# 1541-3z.net
KiCad netlist of a schematic drawn in EAGLE
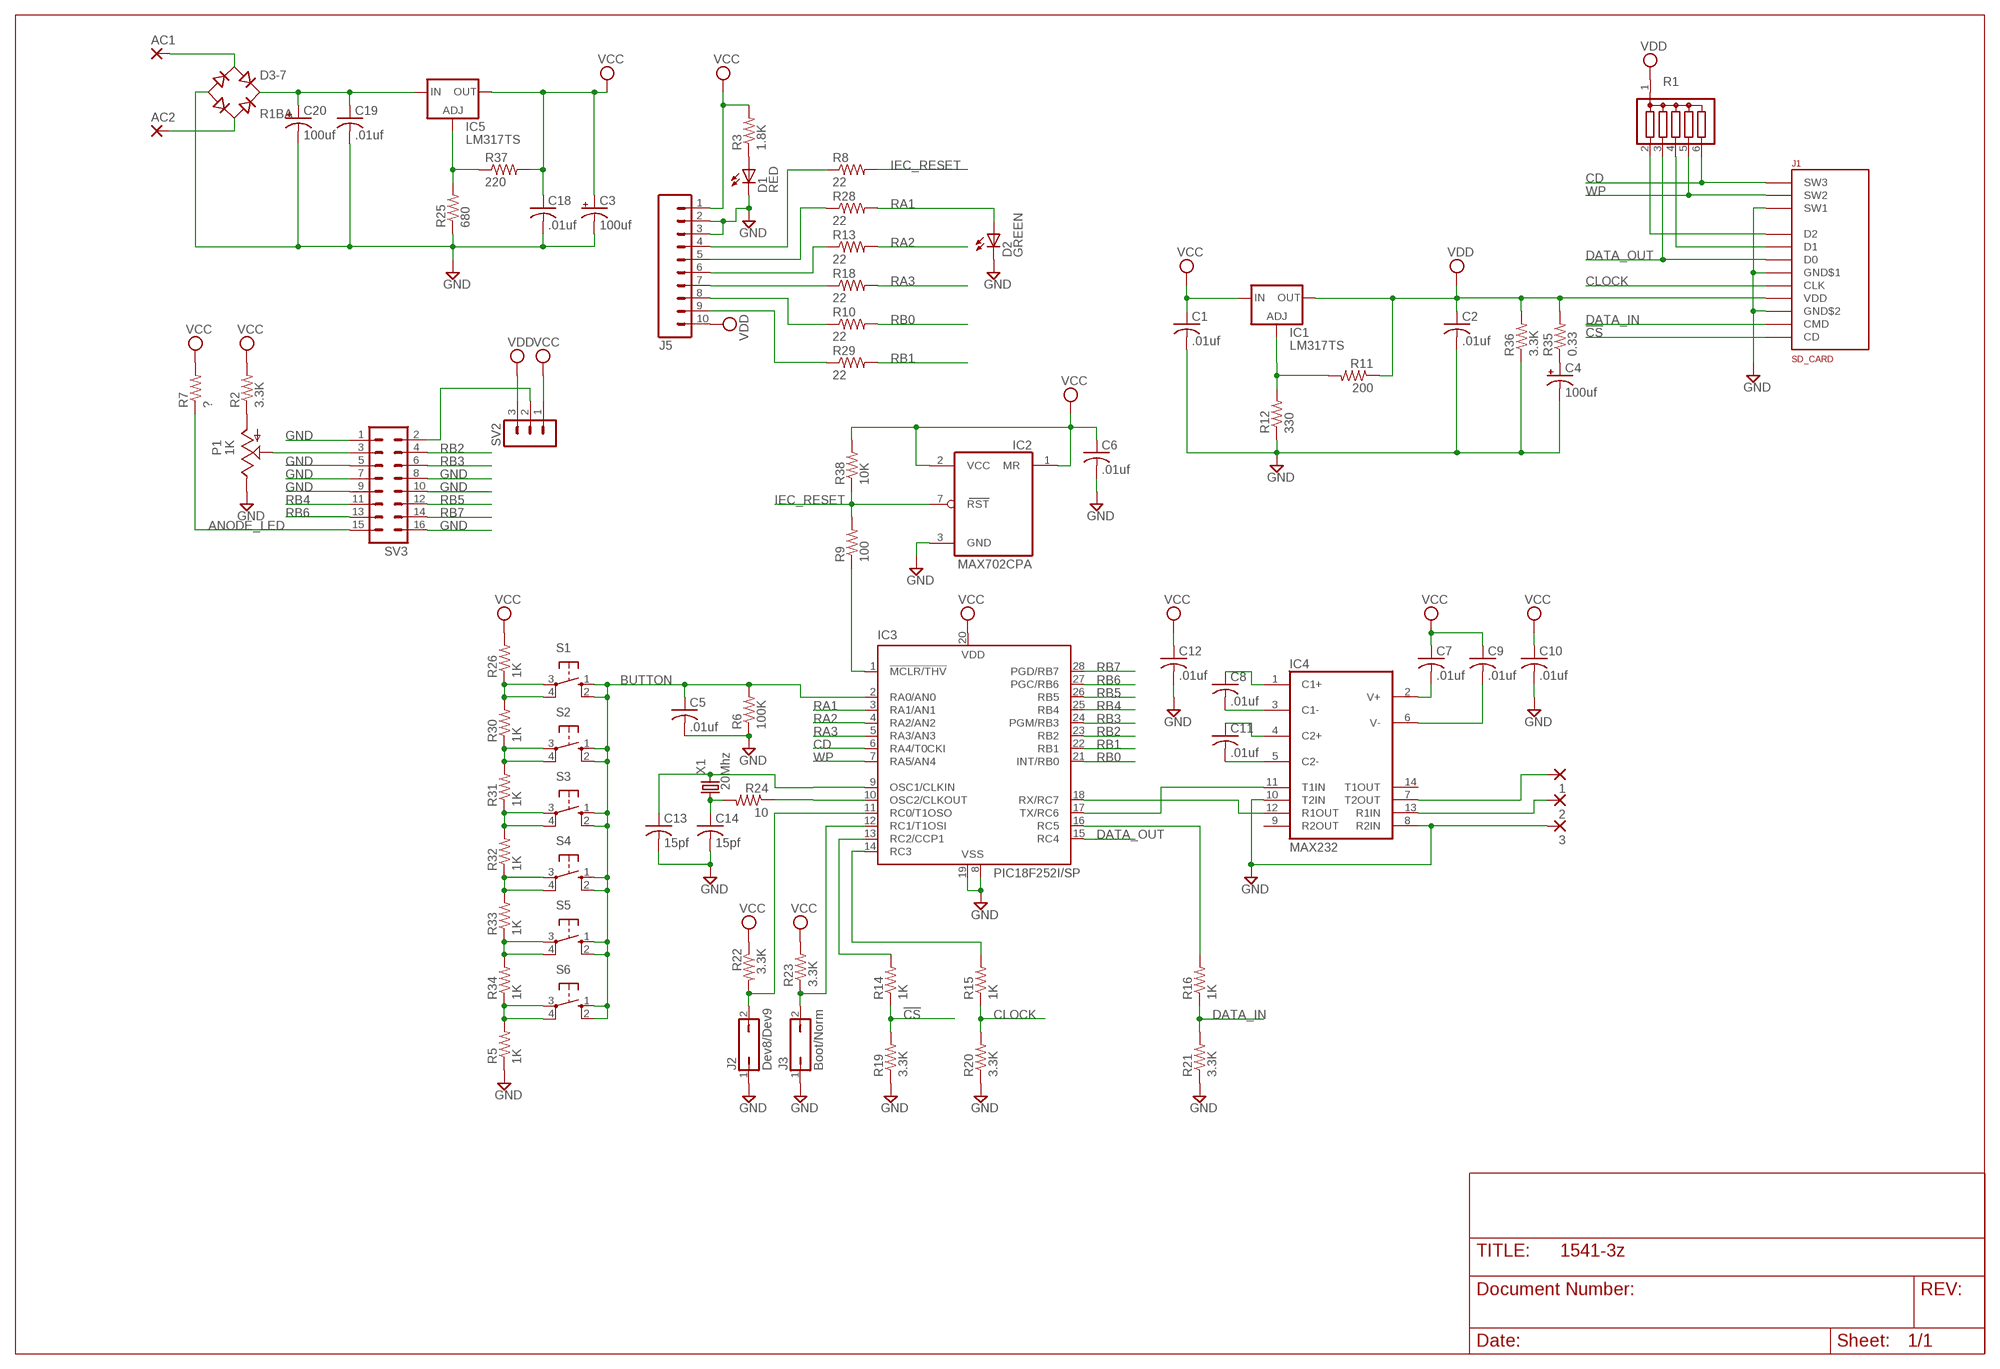
[diagram p0: schematic, sheet 1]

(export (version "E")
  (design (tool "Eeschema 10.0.6"))
  (components
    (comp (ref "1")
      (value "2,15/1,0")
      (footprint "eagle-import:2,15_1,0")
      (libsource (lib "eagle-import") (part "2,15/1,0"))
    )
    (comp (ref "2")
      (value "2,15/1,0")
      (footprint "eagle-import:2,15_1,0")
      (libsource (lib "eagle-import") (part "2,15/1,0"))
    )
    (comp (ref "3")
      (value "2,15/1,0")
      (footprint "eagle-import:2,15_1,0")
      (libsource (lib "eagle-import") (part "2,15/1,0"))
    )
    (comp (ref "AC1")
      (value "2,15/1,0")
      (footprint "eagle-import:2,15_1,0")
      (libsource (lib "eagle-import") (part "2,15/1,0"))
    )
    (comp (ref "AC2")
      (value "2,15/1,0")
      (footprint "eagle-import:2,15_1,0")
      (libsource (lib "eagle-import") (part "2,15/1,0"))
    )
    (comp (ref "C1")
      (value ".01uf")
      (footprint "eagle-import:C025-024X044")
      (libsource (lib "eagle-import") (part "C-US025-024X044"))
    )
    (comp (ref "C2")
      (value ".01uf")
      (footprint "eagle-import:C025-024X044")
      (libsource (lib "eagle-import") (part "C-US025-024X044"))
    )
    (comp (ref "C3")
      (value "100uf")
      (footprint "eagle-import:E2-5")
      (libsource (lib "eagle-import") (part "CPOL-USE2-5"))
    )
    (comp (ref "C4")
      (value "100uf")
      (footprint "eagle-import:E2-5")
      (libsource (lib "eagle-import") (part "CPOL-USE2-5"))
    )
    (comp (ref "C5")
      (value ".01uf")
      (footprint "eagle-import:C025-024X044")
      (libsource (lib "eagle-import") (part "C-US025-024X044"))
    )
    (comp (ref "C6")
      (value ".01uf")
      (footprint "eagle-import:C025-024X044")
      (libsource (lib "eagle-import") (part "C-US025-024X044"))
    )
    (comp (ref "C7")
      (value ".01uf")
      (footprint "eagle-import:C025-024X044")
      (libsource (lib "eagle-import") (part "C-US025-024X044"))
    )
    (comp (ref "C8")
      (value ".01uf")
      (footprint "eagle-import:C025-024X044")
      (libsource (lib "eagle-import") (part "C-US025-024X044"))
    )
    (comp (ref "C9")
      (value ".01uf")
      (footprint "eagle-import:C025-024X044")
      (libsource (lib "eagle-import") (part "C-US025-024X044"))
    )
    (comp (ref "C10")
      (value ".01uf")
      (footprint "eagle-import:C025-024X044")
      (libsource (lib "eagle-import") (part "C-US025-024X044"))
    )
    (comp (ref "C11")
      (value ".01uf")
      (footprint "eagle-import:C025-024X044")
      (libsource (lib "eagle-import") (part "C-US025-024X044"))
    )
    (comp (ref "C12")
      (value ".01uf")
      (footprint "eagle-import:C025-024X044")
      (libsource (lib "eagle-import") (part "C-US025-024X044"))
    )
    (comp (ref "C13")
      (value "15pf")
      (footprint "eagle-import:C025-024X044")
      (libsource (lib "eagle-import") (part "C-US025-024X044"))
    )
    (comp (ref "C14")
      (value "15pf")
      (footprint "eagle-import:C025-024X044")
      (libsource (lib "eagle-import") (part "C-US025-024X044"))
    )
    (comp (ref "C18")
      (value ".01uf")
      (footprint "eagle-import:C025-024X044")
      (libsource (lib "eagle-import") (part "C-US025-024X044"))
    )
    (comp (ref "C19")
      (value ".01uf")
      (footprint "eagle-import:C025-024X044")
      (libsource (lib "eagle-import") (part "C-US025-024X044"))
    )
    (comp (ref "C20")
      (value "100uf")
      (footprint "eagle-import:E2-5")
      (libsource (lib "eagle-import") (part "CPOL-USE2-5"))
    )
    (comp (ref "D1")
      (value "RED")
      (footprint "eagle-import:LED3MM")
      (libsource (lib "eagle-import") (part "LED3MM"))
    )
    (comp (ref "D2")
      (value "GREEN")
      (footprint "eagle-import:LED3MM")
      (libsource (lib "eagle-import") (part "LED3MM"))
    )
    (comp (ref "D3-7")
      (value "R1BA")
      (footprint "eagle-import:RB1A")
      (libsource (lib "eagle-import") (part "RB1A"))
    )
    (comp (ref "IC1")
      (value "LM317TS")
      (footprint "eagle-import:317TS")
      (libsource (lib "eagle-import") (part "LM317TS"))
    )
    (comp (ref "IC2")
      (value "MAX702CPA")
      (footprint "eagle-import:DIL08")
      (fields (field (name "MF") "MAXIM") (field (name "MPN") "MAX702CPA+"))
      (libsource (lib "eagle-import") (part "MAX702CPA"))
    )
    (comp (ref "IC3")
      (value "PIC18F252I/SP")
      (footprint "eagle-import:DIL28-3")
      (fields (field (name "MF") "MICROCHIP") (field (name "MPN") "PIC16F870-I/SP"))
      (libsource (lib "eagle-import") (part "PIC16870PF"))
    )
    (comp (ref "IC4")
      (value "MAX232")
      (footprint "eagle-import:DIL16")
      (fields (field (name "MF") "MAXIM") (field (name "MPN") "MAX232ACPE+"))
      (libsource (lib "eagle-import") (part "MAX232"))
    )
    (comp (ref "IC5")
      (value "LM317TS")
      (footprint "eagle-import:317TS")
      (libsource (lib "eagle-import") (part "LM317TS"))
    )
    (comp (ref "J1")
      (value "SD_CARD")
      (footprint "eagle-import:SD_CARD")
      (libsource (lib "eagle-import") (part "SD_CARD"))
    )
    (comp (ref "J2")
      (value "Dev8/Dev9")
      (footprint "eagle-import:JP1")
      (libsource (lib "eagle-import") (part "JP1Q"))
    )
    (comp (ref "J3")
      (value "Boot/Norm")
      (footprint "eagle-import:JP1")
      (libsource (lib "eagle-import") (part "JP1Q"))
    )
    (comp (ref "J5")
      (value "M10")
      (footprint "eagle-import:10P")
      (libsource (lib "eagle-import") (part "M10"))
    )
    (comp (ref "P1")
      (value "1K")
      (footprint "eagle-import:LI10")
      (libsource (lib "eagle-import") (part "TRIM_US-LI10"))
    )
    (comp (ref "R1")
      (value "G05R")
      (footprint "eagle-import:SIL6")
      (libsource (lib "eagle-import") (part "G05R"))
    )
    (comp (ref "R2")
      (value "3.3K")
      (footprint "eagle-import:0207_2V")
      (libsource (lib "eagle-import") (part "R-US_0207/2V"))
    )
    (comp (ref "R3")
      (value "1.8K")
      (footprint "eagle-import:0207_2V")
      (libsource (lib "eagle-import") (part "R-US_0207/2V"))
    )
    (comp (ref "R5")
      (value "1K")
      (footprint "eagle-import:0207_2V")
      (libsource (lib "eagle-import") (part "R-US_0207/2V"))
    )
    (comp (ref "R6")
      (value "100K")
      (footprint "eagle-import:0207_2V")
      (libsource (lib "eagle-import") (part "R-US_0207/2V"))
    )
    (comp (ref "R7")
      (value "?")
      (footprint "eagle-import:0207_2V")
      (libsource (lib "eagle-import") (part "R-US_0207/2V"))
    )
    (comp (ref "R8")
      (value "22")
      (footprint "eagle-import:0207_2V")
      (libsource (lib "eagle-import") (part "R-US_0207/2V"))
    )
    (comp (ref "R9")
      (value "100")
      (footprint "eagle-import:0207_2V")
      (libsource (lib "eagle-import") (part "R-US_0207/2V"))
    )
    (comp (ref "R10")
      (value "22")
      (footprint "eagle-import:0207_2V")
      (libsource (lib "eagle-import") (part "R-US_0207/2V"))
    )
    (comp (ref "R11")
      (value "200")
      (footprint "eagle-import:0207_2V")
      (libsource (lib "eagle-import") (part "R-US_0207/2V"))
    )
    (comp (ref "R12")
      (value "330")
      (footprint "eagle-import:0207_2V")
      (libsource (lib "eagle-import") (part "R-US_0207/2V"))
    )
    (comp (ref "R13")
      (value "22")
      (footprint "eagle-import:0207_2V")
      (libsource (lib "eagle-import") (part "R-US_0207/2V"))
    )
    (comp (ref "R14")
      (value "1K")
      (footprint "eagle-import:0207_2V")
      (libsource (lib "eagle-import") (part "R-US_0207/2V"))
    )
    (comp (ref "R15")
      (value "1K")
      (footprint "eagle-import:0207_2V")
      (libsource (lib "eagle-import") (part "R-US_0207/2V"))
    )
    (comp (ref "R16")
      (value "1K")
      (footprint "eagle-import:0207_2V")
      (libsource (lib "eagle-import") (part "R-US_0207/2V"))
    )
    (comp (ref "R18")
      (value "22")
      (footprint "eagle-import:0207_2V")
      (libsource (lib "eagle-import") (part "R-US_0207/2V"))
    )
    (comp (ref "R19")
      (value "3.3K")
      (footprint "eagle-import:0207_2V")
      (libsource (lib "eagle-import") (part "R-US_0207/2V"))
    )
    (comp (ref "R20")
      (value "3.3K")
      (footprint "eagle-import:0207_2V")
      (libsource (lib "eagle-import") (part "R-US_0207/2V"))
    )
    (comp (ref "R21")
      (value "3.3K")
      (footprint "eagle-import:0207_2V")
      (libsource (lib "eagle-import") (part "R-US_0207/2V"))
    )
    (comp (ref "R22")
      (value "3.3K")
      (footprint "eagle-import:0207_2V")
      (libsource (lib "eagle-import") (part "R-US_0207/2V"))
    )
    (comp (ref "R23")
      (value "3.3K")
      (footprint "eagle-import:0207_2V")
      (libsource (lib "eagle-import") (part "R-US_0207/2V"))
    )
    (comp (ref "R24")
      (value "10")
      (footprint "eagle-import:0207_2V")
      (libsource (lib "eagle-import") (part "R-US_0207/2V"))
    )
    (comp (ref "R25")
      (value "680")
      (footprint "eagle-import:0207_2V")
      (libsource (lib "eagle-import") (part "R-US_0207/2V"))
    )
    (comp (ref "R26")
      (value "1K")
      (footprint "eagle-import:0207_2V")
      (libsource (lib "eagle-import") (part "R-US_0207/2V"))
    )
    (comp (ref "R28")
      (value "22")
      (footprint "eagle-import:0207_2V")
      (libsource (lib "eagle-import") (part "R-US_0207/2V"))
    )
    (comp (ref "R29")
      (value "22")
      (footprint "eagle-import:0207_2V")
      (libsource (lib "eagle-import") (part "R-US_0207/2V"))
    )
    (comp (ref "R30")
      (value "1K")
      (footprint "eagle-import:0207_2V")
      (libsource (lib "eagle-import") (part "R-US_0207/2V"))
    )
    (comp (ref "R31")
      (value "1K")
      (footprint "eagle-import:0207_2V")
      (libsource (lib "eagle-import") (part "R-US_0207/2V"))
    )
    (comp (ref "R32")
      (value "1K")
      (footprint "eagle-import:0207_2V")
      (libsource (lib "eagle-import") (part "R-US_0207/2V"))
    )
    (comp (ref "R33")
      (value "1K")
      (footprint "eagle-import:0207_2V")
      (libsource (lib "eagle-import") (part "R-US_0207/2V"))
    )
    (comp (ref "R34")
      (value "1K")
      (footprint "eagle-import:0207_2V")
      (libsource (lib "eagle-import") (part "R-US_0207/2V"))
    )
    (comp (ref "R35")
      (value "0.33")
      (footprint "eagle-import:0207_2V")
      (libsource (lib "eagle-import") (part "R-US_0207/2V"))
    )
    (comp (ref "R36")
      (value "3.3K")
      (footprint "eagle-import:0207_2V")
      (libsource (lib "eagle-import") (part "R-US_0207/2V"))
    )
    (comp (ref "R37")
      (value "220")
      (footprint "eagle-import:0207_2V")
      (libsource (lib "eagle-import") (part "R-US_0207/2V"))
    )
    (comp (ref "R38")
      (value "10K")
      (footprint "eagle-import:0207_2V")
      (libsource (lib "eagle-import") (part "R-US_0207/2V"))
    )
    (comp (ref "S1")
      (value "10-XX")
      (footprint "eagle-import:B3F-10XX")
      (fields (field (name "MPN") "B3F-1000"))
      (libsource (lib "eagle-import") (part "10-XX"))
    )
    (comp (ref "S2")
      (value "10-XX")
      (footprint "eagle-import:B3F-10XX")
      (fields (field (name "MPN") "B3F-1000"))
      (libsource (lib "eagle-import") (part "10-XX"))
    )
    (comp (ref "S3")
      (value "10-XX")
      (footprint "eagle-import:B3F-10XX")
      (fields (field (name "MPN") "B3F-1000"))
      (libsource (lib "eagle-import") (part "10-XX"))
    )
    (comp (ref "S4")
      (value "10-XX")
      (footprint "eagle-import:B3F-10XX")
      (fields (field (name "MPN") "B3F-1000"))
      (libsource (lib "eagle-import") (part "10-XX"))
    )
    (comp (ref "S5")
      (value "10-XX")
      (footprint "eagle-import:B3F-10XX")
      (fields (field (name "MPN") "B3F-1000"))
      (libsource (lib "eagle-import") (part "10-XX"))
    )
    (comp (ref "S6")
      (value "10-XX")
      (footprint "eagle-import:B3F-10XX")
      (fields (field (name "MPN") "B3F-1000"))
      (libsource (lib "eagle-import") (part "10-XX"))
    )
    (comp (ref "SV2")
      (value "MA03-1")
      (footprint "eagle-import:MA03-1")
      (libsource (lib "eagle-import") (part "MA03-1"))
    )
    (comp (ref "SV3")
      (value "ML16")
      (footprint "eagle-import:ML16")
      (libsource (lib "eagle-import") (part "ML16"))
    )
    (comp (ref "X1")
      (value "20Mhz")
      (footprint "eagle-import:HC49U70")
      (libsource (lib "eagle-import") (part "CRYSTALHC49U70"))
    )
  )
  (nets
    (net (code "1") (name "/ANODE_LED") (class "Default")
      (node (ref "R7") (pin "1") (pinfunction "1_1") (pintype "passive"))
      (node (ref "SV3") (pin "15") (pinfunction "15_15") (pintype "passive"))
    )
    (net (code "2") (name "/BUTTON") (class "Default")
      (node (ref "C5") (pin "1") (pinfunction "1_1") (pintype "passive"))
      (node (ref "IC3") (pin "2") (pinfunction "RA0/AN0_2") (pintype "bidirectional"))
      (node (ref "R6") (pin "2") (pinfunction "2_2") (pintype "passive"))
      (node (ref "S1") (pin "1") (pinfunction "S_1") (pintype "passive"))
      (node (ref "S1") (pin "2") (pinfunction "S1_2") (pintype "passive"))
      (node (ref "S2") (pin "1") (pinfunction "S_1") (pintype "passive"))
      (node (ref "S2") (pin "2") (pinfunction "S1_2") (pintype "passive"))
      (node (ref "S3") (pin "1") (pinfunction "S_1") (pintype "passive"))
      (node (ref "S3") (pin "2") (pinfunction "S1_2") (pintype "passive"))
      (node (ref "S4") (pin "1") (pinfunction "S_1") (pintype "passive"))
      (node (ref "S4") (pin "2") (pinfunction "S1_2") (pintype "passive"))
      (node (ref "S5") (pin "1") (pinfunction "S_1") (pintype "passive"))
      (node (ref "S5") (pin "2") (pinfunction "S1_2") (pintype "passive"))
      (node (ref "S6") (pin "1") (pinfunction "S_1") (pintype "passive"))
      (node (ref "S6") (pin "2") (pinfunction "S1_2") (pintype "passive"))
    )
    (net (code "3") (name "/CD") (class "Default")
      (node (ref "IC3") (pin "6") (pinfunction "RA4/T0CKI_6") (pintype "bidirectional"))
      (node (ref "J1") (pin "SW3") (pinfunction "SW3_SW3") (pintype "output"))
      (node (ref "R1") (pin "6") (pinfunction "6_6") (pintype "passive"))
    )
    (net (code "4") (name "/CLOCK") (class "Default")
      (node (ref "J1") (pin "CLK") (pinfunction "CLK_CLK") (pintype "input"))
      (node (ref "R15") (pin "1") (pinfunction "1_1") (pintype "passive"))
      (node (ref "R20") (pin "2") (pinfunction "2_2") (pintype "passive"))
    )
    (net (code "5") (name "/DATA_IN") (class "Default")
      (node (ref "J1") (pin "CMD") (pinfunction "CMD_CMD") (pintype "input"))
      (node (ref "R16") (pin "1") (pinfunction "1_1") (pintype "passive"))
      (node (ref "R21") (pin "2") (pinfunction "2_2") (pintype "passive"))
    )
    (net (code "6") (name "/DATA_OUT") (class "Default")
      (node (ref "IC3") (pin "15") (pinfunction "RC4_15") (pintype "bidirectional"))
      (node (ref "J1") (pin "DAT0") (pinfunction "D0_DAT0") (pintype "output"))
      (node (ref "R1") (pin "3") (pinfunction "3_3") (pintype "passive"))
    )
    (net (code "7") (name "/IEC_RESET") (class "Default")
      (node (ref "IC2") (pin "7") (pinfunction "RST_7") (pintype "output"))
      (node (ref "R38") (pin "1") (pinfunction "1_1") (pintype "passive"))
      (node (ref "R8") (pin "2") (pinfunction "2_2") (pintype "passive"))
      (node (ref "R9") (pin "2") (pinfunction "2_2") (pintype "passive"))
    )
    (net (code "8") (name "/RA1") (class "Default")
      (node (ref "D2") (pin "A") (pinfunction "A_A") (pintype "passive"))
      (node (ref "IC3") (pin "3") (pinfunction "RA1/AN1_3") (pintype "bidirectional"))
      (node (ref "R28") (pin "2") (pinfunction "2_2") (pintype "passive"))
    )
    (net (code "9") (name "/RA2") (class "Default")
      (node (ref "IC3") (pin "4") (pinfunction "RA2/AN2_4") (pintype "bidirectional"))
      (node (ref "R13") (pin "2") (pinfunction "2_2") (pintype "passive"))
    )
    (net (code "10") (name "/RA3") (class "Default")
      (node (ref "IC3") (pin "5") (pinfunction "RA3/AN3_5") (pintype "bidirectional"))
      (node (ref "R18") (pin "2") (pinfunction "2_2") (pintype "passive"))
    )
    (net (code "11") (name "/RB0") (class "Default")
      (node (ref "IC3") (pin "21") (pinfunction "INT/RB0_21") (pintype "bidirectional"))
      (node (ref "R10") (pin "2") (pinfunction "2_2") (pintype "passive"))
    )
    (net (code "12") (name "/RB1") (class "Default")
      (node (ref "IC3") (pin "22") (pinfunction "RB1_22") (pintype "bidirectional"))
      (node (ref "R29") (pin "2") (pinfunction "2_2") (pintype "passive"))
    )
    (net (code "13") (name "/RB2") (class "Default")
      (node (ref "IC3") (pin "23") (pinfunction "RB2_23") (pintype "bidirectional"))
      (node (ref "SV3") (pin "4") (pinfunction "4_4") (pintype "passive"))
    )
    (net (code "14") (name "/RB3") (class "Default")
      (node (ref "IC3") (pin "24") (pinfunction "PGM/RB3_24") (pintype "bidirectional"))
      (node (ref "SV3") (pin "6") (pinfunction "6_6") (pintype "passive"))
    )
    (net (code "15") (name "/RB4") (class "Default")
      (node (ref "IC3") (pin "25") (pinfunction "RB4_25") (pintype "bidirectional"))
      (node (ref "SV3") (pin "11") (pinfunction "11_11") (pintype "passive"))
    )
    (net (code "16") (name "/RB5") (class "Default")
      (node (ref "IC3") (pin "26") (pinfunction "RB5_26") (pintype "bidirectional"))
      (node (ref "SV3") (pin "12") (pinfunction "12_12") (pintype "passive"))
    )
    (net (code "17") (name "/RB6") (class "Default")
      (node (ref "IC3") (pin "27") (pinfunction "PGC/RB6_27") (pintype "bidirectional"))
      (node (ref "SV3") (pin "13") (pinfunction "13_13") (pintype "passive"))
    )
    (net (code "18") (name "/RB7") (class "Default")
      (node (ref "IC3") (pin "28") (pinfunction "PGD/RB7_28") (pintype "bidirectional"))
      (node (ref "SV3") (pin "14") (pinfunction "14_14") (pintype "passive"))
    )
    (net (code "19") (name "/WP") (class "Default")
      (node (ref "IC3") (pin "7") (pinfunction "RA5/AN4_7") (pintype "bidirectional"))
      (node (ref "J1") (pin "SW2") (pinfunction "SW2_SW2") (pintype "output"))
      (node (ref "R1") (pin "5") (pinfunction "5_5") (pintype "passive"))
    )
    (net (code "20") (name "/~{CS}") (class "Default")
      (node (ref "J1") (pin "DAT3") (pinfunction "CD_DAT3") (pintype "input"))
      (node (ref "R14") (pin "1") (pinfunction "1_1") (pintype "passive"))
      (node (ref "R19") (pin "2") (pinfunction "2_2") (pintype "passive"))
    )
    (net (code "21") (name "GND") (class "Default")
      (node (ref "3") (pin "1") (pinfunction "P_1") (pintype "passive"))
      (node (ref "C1") (pin "2") (pinfunction "2_2") (pintype "passive"))
      (node (ref "C10") (pin "2") (pinfunction "2_2") (pintype "passive"))
      (node (ref "C12") (pin "2") (pinfunction "2_2") (pintype "passive"))
      (node (ref "C13") (pin "2") (pinfunction "2_2") (pintype "passive"))
      (node (ref "C14") (pin "2") (pinfunction "2_2") (pintype "passive"))
      (node (ref "C18") (pin "2") (pinfunction "2_2") (pintype "passive"))
      (node (ref "C19") (pin "2") (pinfunction "2_2") (pintype "passive"))
      (node (ref "C2") (pin "2") (pinfunction "2_2") (pintype "passive"))
      (node (ref "C20") (pin "-") (pinfunction "-_-") (pintype "passive"))
      (node (ref "C3") (pin "-") (pinfunction "-_-") (pintype "passive"))
      (node (ref "C4") (pin "-") (pinfunction "-_-") (pintype "passive"))
      (node (ref "C5") (pin "2") (pinfunction "2_2") (pintype "passive"))
      (node (ref "C6") (pin "2") (pinfunction "2_2") (pintype "passive"))
      (node (ref "D1") (pin "K") (pinfunction "C_K") (pintype "passive"))
      (node (ref "D2") (pin "K") (pinfunction "C_K") (pintype "passive"))
      (node (ref "D3-7") (pin "-") (pinfunction "-_-") (pintype "passive"))
      (node (ref "IC2") (pin "3") (pinfunction "GND_3") (pintype "power_in"))
      (node (ref "IC3") (pin "19") (pinfunction "VSS_19") (pintype "power_in"))
      (node (ref "IC3") (pin "8") (pinfunction "VSS_8") (pintype "power_in"))
      (node (ref "IC4") (pin "10") (pinfunction "T2IN_10") (pintype "input"))
      (node (ref "IC4") (pin "8") (pinfunction "R2IN_8") (pintype "input"))
      (node (ref "J1") (pin "SW1") (pinfunction "SW1_SW1") (pintype "input"))
      (node (ref "J1") (pin "VSS$1") (pinfunction "GND$1_VSS$1") (pintype "power_in"))
      (node (ref "J1") (pin "VSS$2") (pinfunction "GND$2_VSS$2") (pintype "power_in"))
      (node (ref "J2") (pin "1") (pinfunction "1_1") (pintype "passive"))
      (node (ref "J3") (pin "1") (pinfunction "1_1") (pintype "passive"))
      (node (ref "J5") (pin "2") (pinfunction "2_2") (pintype "passive"))
      (node (ref "J5") (pin "3") (pinfunction "3_3") (pintype "passive"))
      (node (ref "P1") (pin "E") (pinfunction "E_E") (pintype "passive"))
      (node (ref "R12") (pin "1") (pinfunction "1_1") (pintype "passive"))
      (node (ref "R19") (pin "1") (pinfunction "1_1") (pintype "passive"))
      (node (ref "R20") (pin "1") (pinfunction "1_1") (pintype "passive"))
      (node (ref "R21") (pin "1") (pinfunction "1_1") (pintype "passive"))
      (node (ref "R25") (pin "1") (pinfunction "1_1") (pintype "passive"))
      (node (ref "R36") (pin "1") (pinfunction "1_1") (pintype "passive"))
      (node (ref "R5") (pin "1") (pinfunction "1_1") (pintype "passive"))
      (node (ref "R6") (pin "1") (pinfunction "1_1") (pintype "passive"))
      (node (ref "SV3") (pin "1") (pinfunction "1_1") (pintype "passive"))
      (node (ref "SV3") (pin "10") (pinfunction "10_10") (pintype "passive"))
      (node (ref "SV3") (pin "16") (pinfunction "16_16") (pintype "passive"))
      (node (ref "SV3") (pin "5") (pinfunction "5_5") (pintype "passive"))
      (node (ref "SV3") (pin "7") (pinfunction "7_7") (pintype "passive"))
      (node (ref "SV3") (pin "8") (pinfunction "8_8") (pintype "passive"))
      (node (ref "SV3") (pin "9") (pinfunction "9_9") (pintype "passive"))
    )
    (net (code "22") (name "Net-(1-P)") (class "Default")
      (node (ref "1") (pin "1") (pinfunction "P_1") (pintype "passive"))
      (node (ref "IC4") (pin "7") (pinfunction "T2OUT_7") (pintype "output"))
    )
    (net (code "23") (name "Net-(2-P)") (class "Default")
      (node (ref "2") (pin "1") (pinfunction "P_1") (pintype "passive"))
      (node (ref "IC4") (pin "13") (pinfunction "R1IN_13") (pintype "input"))
    )
    (net (code "24") (name "Net-(AC1-P)") (class "Default")
      (node (ref "AC1") (pin "1") (pinfunction "P_1") (pintype "passive"))
      (node (ref "D3-7") (pin "AC1") (pinfunction "AC1_AC1") (pintype "passive"))
    )
    (net (code "25") (name "Net-(AC2-P)") (class "Default")
      (node (ref "AC2") (pin "1") (pinfunction "P_1") (pintype "passive"))
      (node (ref "D3-7") (pin "AC2") (pinfunction "AC2_AC2") (pintype "passive"))
    )
    (net (code "26") (name "Net-(C4-Pad+)") (class "Default")
      (node (ref "C4") (pin "+") (pinfunction "+_+") (pintype "passive"))
      (node (ref "R35") (pin "1") (pinfunction "1_1") (pintype "passive"))
    )
    (net (code "27") (name "Net-(C14-Pad1)") (class "Default")
      (node (ref "C14") (pin "1") (pinfunction "1_1") (pintype "passive"))
      (node (ref "R24") (pin "2") (pinfunction "2_2") (pintype "passive"))
      (node (ref "X1") (pin "1") (pinfunction "1_1") (pintype "passive"))
    )
    (net (code "28") (name "Net-(D1-PadA)") (class "Default")
      (node (ref "D1") (pin "A") (pinfunction "A_A") (pintype "passive"))
      (node (ref "R3") (pin "1") (pinfunction "1_1") (pintype "passive"))
    )
    (net (code "29") (name "Net-(IC1-ADJ)") (class "Default")
      (node (ref "IC1") (pin "1") (pinfunction "ADJ_1") (pintype "input"))
      (node (ref "R11") (pin "2") (pinfunction "2_2") (pintype "passive"))
      (node (ref "R12") (pin "2") (pinfunction "2_2") (pintype "passive"))
    )
    (net (code "30") (name "Net-(IC3-OSC1{slash}CLKIN)") (class "Default")
      (node (ref "C13") (pin "1") (pinfunction "1_1") (pintype "passive"))
      (node (ref "IC3") (pin "9") (pinfunction "OSC1/CLKIN_9") (pintype "input"))
      (node (ref "X1") (pin "2") (pinfunction "2_2") (pintype "passive"))
    )
    (net (code "31") (name "Net-(IC3-OSC2{slash}CLKOUT)") (class "Default")
      (node (ref "IC3") (pin "10") (pinfunction "OSC2/CLKOUT_10") (pintype "output"))
      (node (ref "R24") (pin "1") (pinfunction "1_1") (pintype "passive"))
    )
    (net (code "32") (name "Net-(IC3-RC0{slash}T1OSO)") (class "Default")
      (node (ref "IC3") (pin "11") (pinfunction "RC0/T1OSO_11") (pintype "bidirectional"))
      (node (ref "J2") (pin "2") (pinfunction "2_2") (pintype "passive"))
      (node (ref "R22") (pin "2") (pinfunction "2_2") (pintype "passive"))
    )
    (net (code "33") (name "Net-(IC3-RC1{slash}T1OSI)") (class "Default")
      (node (ref "IC3") (pin "12") (pinfunction "RC1/T1OSI_12") (pintype "bidirectional"))
      (node (ref "J3") (pin "2") (pinfunction "2_2") (pintype "passive"))
      (node (ref "R23") (pin "1") (pinfunction "1_1") (pintype "passive"))
    )
    (net (code "34") (name "Net-(IC3-RC2{slash}CCP1)") (class "Default")
      (node (ref "IC3") (pin "13") (pinfunction "RC2/CCP1_13") (pintype "bidirectional"))
      (node (ref "R14") (pin "2") (pinfunction "2_2") (pintype "passive"))
    )
    (net (code "35") (name "Net-(IC3-RC3)") (class "Default")
      (node (ref "IC3") (pin "14") (pinfunction "RC3_14") (pintype "bidirectional"))
      (node (ref "R15") (pin "2") (pinfunction "2_2") (pintype "passive"))
    )
    (net (code "36") (name "Net-(IC3-RC5)") (class "Default")
      (node (ref "IC3") (pin "16") (pinfunction "RC5_16") (pintype "bidirectional"))
      (node (ref "R16") (pin "2") (pinfunction "2_2") (pintype "passive"))
    )
    (net (code "37") (name "Net-(IC3-RX{slash}RC7)") (class "Default")
      (node (ref "IC3") (pin "18") (pinfunction "RX/RC7_18") (pintype "bidirectional"))
      (node (ref "IC4") (pin "12") (pinfunction "R1OUT_12") (pintype "output"))
    )
    (net (code "38") (name "Net-(IC3-TX{slash}RC6)") (class "Default")
      (node (ref "IC3") (pin "17") (pinfunction "TX/RC6_17") (pintype "bidirectional"))
      (node (ref "IC4") (pin "11") (pinfunction "T1IN_11") (pintype "input"))
    )
    (net (code "39") (name "Net-(IC3-~{MCLR{slash}THV})") (class "Default")
      (node (ref "IC3") (pin "1") (pinfunction "~{MCLR/THV}_1") (pintype "input"))
      (node (ref "R9") (pin "1") (pinfunction "1_1") (pintype "passive"))
    )
    (net (code "40") (name "Net-(IC4A-C1+)") (class "Default")
      (node (ref "C8") (pin "1") (pinfunction "1_1") (pintype "passive"))
      (node (ref "IC4") (pin "1") (pinfunction "C1+_1") (pintype "bidirectional"))
    )
    (net (code "41") (name "Net-(IC4A-C1-)") (class "Default")
      (node (ref "C8") (pin "2") (pinfunction "2_2") (pintype "passive"))
      (node (ref "IC4") (pin "3") (pinfunction "C1-_3") (pintype "bidirectional"))
    )
    (net (code "42") (name "Net-(IC4A-C2+)") (class "Default")
      (node (ref "C11") (pin "1") (pinfunction "1_1") (pintype "passive"))
      (node (ref "IC4") (pin "4") (pinfunction "C2+_4") (pintype "bidirectional"))
    )
    (net (code "43") (name "Net-(IC4A-C2-)") (class "Default")
      (node (ref "C11") (pin "2") (pinfunction "2_2") (pintype "passive"))
      (node (ref "IC4") (pin "5") (pinfunction "C2-_5") (pintype "bidirectional"))
    )
    (net (code "44") (name "Net-(IC4A-V+)") (class "Default")
      (node (ref "C7") (pin "2") (pinfunction "2_2") (pintype "passive"))
      (node (ref "IC4") (pin "2") (pinfunction "V+_2") (pintype "bidirectional"))
    )
    (net (code "45") (name "Net-(IC4A-V-)") (class "Default")
      (node (ref "C9") (pin "2") (pinfunction "2_2") (pintype "passive"))
      (node (ref "IC4") (pin "6") (pinfunction "V-_6") (pintype "bidirectional"))
    )
    (net (code "46") (name "Net-(IC5-ADJ)") (class "Default")
      (node (ref "IC5") (pin "1") (pinfunction "ADJ_1") (pintype "input"))
      (node (ref "R25") (pin "2") (pinfunction "2_2") (pintype "passive"))
      (node (ref "R37") (pin "1") (pinfunction "1_1") (pintype "passive"))
    )
    (net (code "47") (name "Net-(IC5-IN)") (class "Default")
      (node (ref "C19") (pin "1") (pinfunction "1_1") (pintype "passive"))
      (node (ref "C20") (pin "+") (pinfunction "+_+") (pintype "passive"))
      (node (ref "D3-7") (pin "+") (pinfunction "+_+") (pintype "passive"))
      (node (ref "IC5") (pin "3") (pinfunction "IN_3") (pintype "input"))
    )
    (net (code "48") (name "Net-(J1-D1)") (class "Default")
      (node (ref "J1") (pin "DAT1") (pinfunction "D1_DAT1") (pintype "output"))
      (node (ref "R1") (pin "4") (pinfunction "4_4") (pintype "passive"))
    )
    (net (code "49") (name "Net-(J1-D2)") (class "Default")
      (node (ref "J1") (pin "DAT2") (pinfunction "D2_DAT2") (pintype "output"))
      (node (ref "R1") (pin "2") (pinfunction "2_2") (pintype "passive"))
    )
    (net (code "50") (name "Net-(J5-Pad4)") (class "Default")
      (node (ref "J5") (pin "4") (pinfunction "4_4") (pintype "passive"))
      (node (ref "R8") (pin "1") (pinfunction "1_1") (pintype "passive"))
    )
    (net (code "51") (name "Net-(J5-Pad5)") (class "Default")
      (node (ref "J5") (pin "5") (pinfunction "5_5") (pintype "passive"))
      (node (ref "R28") (pin "1") (pinfunction "1_1") (pintype "passive"))
    )
    (net (code "52") (name "Net-(J5-Pad6)") (class "Default")
      (node (ref "J5") (pin "6") (pinfunction "6_6") (pintype "passive"))
      (node (ref "R13") (pin "1") (pinfunction "1_1") (pintype "passive"))
    )
    (net (code "53") (name "Net-(J5-Pad7)") (class "Default")
      (node (ref "J5") (pin "7") (pinfunction "7_7") (pintype "passive"))
      (node (ref "R18") (pin "1") (pinfunction "1_1") (pintype "passive"))
    )
    (net (code "54") (name "Net-(J5-Pad8)") (class "Default")
      (node (ref "J5") (pin "8") (pinfunction "8_8") (pintype "passive"))
      (node (ref "R10") (pin "1") (pinfunction "1_1") (pintype "passive"))
    )
    (net (code "55") (name "Net-(J5-Pad9)") (class "Default")
      (node (ref "J5") (pin "9") (pinfunction "9_9") (pintype "passive"))
      (node (ref "R29") (pin "1") (pinfunction "1_1") (pintype "passive"))
    )
    (net (code "56") (name "Net-(P1-PadA)") (class "Default")
      (node (ref "P1") (pin "A") (pinfunction "A_A") (pintype "passive"))
      (node (ref "R2") (pin "1") (pinfunction "1_1") (pintype "passive"))
    )
    (net (code "57") (name "Net-(P1-PadS)") (class "Default")
      (node (ref "P1") (pin "S") (pinfunction "S_S") (pintype "passive"))
      (node (ref "SV3") (pin "3") (pinfunction "3_3") (pintype "passive"))
    )
    (net (code "58") (name "Net-(S1-P)") (class "Default")
      (node (ref "R26") (pin "1") (pinfunction "1_1") (pintype "passive"))
      (node (ref "R30") (pin "2") (pinfunction "2_2") (pintype "passive"))
      (node (ref "S1") (pin "3") (pinfunction "P_3") (pintype "passive"))
      (node (ref "S1") (pin "4") (pinfunction "P1_4") (pintype "passive"))
    )
    (net (code "59") (name "Net-(S2-P)") (class "Default")
      (node (ref "R30") (pin "1") (pinfunction "1_1") (pintype "passive"))
      (node (ref "R31") (pin "2") (pinfunction "2_2") (pintype "passive"))
      (node (ref "S2") (pin "3") (pinfunction "P_3") (pintype "passive"))
      (node (ref "S2") (pin "4") (pinfunction "P1_4") (pintype "passive"))
    )
    (net (code "60") (name "Net-(S3-P)") (class "Default")
      (node (ref "R31") (pin "1") (pinfunction "1_1") (pintype "passive"))
      (node (ref "R32") (pin "2") (pinfunction "2_2") (pintype "passive"))
      (node (ref "S3") (pin "3") (pinfunction "P_3") (pintype "passive"))
      (node (ref "S3") (pin "4") (pinfunction "P1_4") (pintype "passive"))
    )
    (net (code "61") (name "Net-(S4-P)") (class "Default")
      (node (ref "R32") (pin "1") (pinfunction "1_1") (pintype "passive"))
      (node (ref "R33") (pin "2") (pinfunction "2_2") (pintype "passive"))
      (node (ref "S4") (pin "3") (pinfunction "P_3") (pintype "passive"))
      (node (ref "S4") (pin "4") (pinfunction "P1_4") (pintype "passive"))
    )
    (net (code "62") (name "Net-(S5-P)") (class "Default")
      (node (ref "R33") (pin "1") (pinfunction "1_1") (pintype "passive"))
      (node (ref "R34") (pin "2") (pinfunction "2_2") (pintype "passive"))
      (node (ref "S5") (pin "3") (pinfunction "P_3") (pintype "passive"))
      (node (ref "S5") (pin "4") (pinfunction "P1_4") (pintype "passive"))
    )
    (net (code "63") (name "Net-(S6-P)") (class "Default")
      (node (ref "R34") (pin "1") (pinfunction "1_1") (pintype "passive"))
      (node (ref "R5") (pin "2") (pinfunction "2_2") (pintype "passive"))
      (node (ref "S6") (pin "3") (pinfunction "P_3") (pintype "passive"))
      (node (ref "S6") (pin "4") (pinfunction "P1_4") (pintype "passive"))
    )
    (net (code "64") (name "Net-(SV2-Pad2)") (class "Default")
      (node (ref "SV2") (pin "2") (pinfunction "2_2") (pintype "passive"))
      (node (ref "SV3") (pin "2") (pinfunction "2_2") (pintype "passive"))
    )
    (net (code "65") (name "VCC") (class "Default")
      (node (ref "C1") (pin "1") (pinfunction "1_1") (pintype "passive"))
      (node (ref "C10") (pin "1") (pinfunction "1_1") (pintype "passive"))
      (node (ref "C12") (pin "1") (pinfunction "1_1") (pintype "passive"))
      (node (ref "C18") (pin "1") (pinfunction "1_1") (pintype "passive"))
      (node (ref "C3") (pin "+") (pinfunction "+_+") (pintype "passive"))
      (node (ref "C6") (pin "1") (pinfunction "1_1") (pintype "passive"))
      (node (ref "C7") (pin "1") (pinfunction "1_1") (pintype "passive"))
      (node (ref "C9") (pin "1") (pinfunction "1_1") (pintype "passive"))
      (node (ref "IC1") (pin "3") (pinfunction "IN_3") (pintype "input"))
      (node (ref "IC2") (pin "1") (pinfunction "MR_1") (pintype "input"))
      (node (ref "IC2") (pin "2") (pinfunction "VCC_2") (pintype "power_in"))
      (node (ref "IC3") (pin "20") (pinfunction "VDD_20") (pintype "power_in"))
      (node (ref "IC5") (pin "2") (pinfunction "OUT_2") (pintype "passive"))
      (node (ref "J5") (pin "1") (pinfunction "1_1") (pintype "passive"))
      (node (ref "R2") (pin "2") (pinfunction "2_2") (pintype "passive"))
      (node (ref "R22") (pin "1") (pinfunction "1_1") (pintype "passive"))
      (node (ref "R23") (pin "2") (pinfunction "2_2") (pintype "passive"))
      (node (ref "R26") (pin "2") (pinfunction "2_2") (pintype "passive"))
      (node (ref "R3") (pin "2") (pinfunction "2_2") (pintype "passive"))
      (node (ref "R37") (pin "2") (pinfunction "2_2") (pintype "passive"))
      (node (ref "R38") (pin "2") (pinfunction "2_2") (pintype "passive"))
      (node (ref "R7") (pin "2") (pinfunction "2_2") (pintype "passive"))
      (node (ref "SV2") (pin "1") (pinfunction "1_1") (pintype "passive"))
    )
    (net (code "66") (name "VDD") (class "Default")
      (node (ref "C2") (pin "1") (pinfunction "1_1") (pintype "passive"))
      (node (ref "IC1") (pin "2") (pinfunction "OUT_2") (pintype "passive"))
      (node (ref "J1") (pin "VDD") (pinfunction "VDD_VDD") (pintype "power_in"))
      (node (ref "J5") (pin "10") (pinfunction "10_10") (pintype "passive"))
      (node (ref "R1") (pin "1") (pinfunction "1_1") (pintype "passive"))
      (node (ref "R11") (pin "1") (pinfunction "1_1") (pintype "passive"))
      (node (ref "R35") (pin "2") (pinfunction "2_2") (pintype "passive"))
      (node (ref "R36") (pin "2") (pinfunction "2_2") (pintype "passive"))
      (node (ref "SV2") (pin "3") (pinfunction "3_3") (pintype "passive"))
    )
    (net (code "67") (name "unconnected-(IC4A-R2OUT-Pad9)") (class "Default")
      (node (ref "IC4") (pin "9") (pinfunction "R2OUT_9") (pintype "output"))
    )
    (net (code "68") (name "unconnected-(IC4A-T1OUT-Pad14)") (class "Default")
      (node (ref "IC4") (pin "14") (pinfunction "T1OUT_14") (pintype "output"))
    )
  )
)
